# Group_01.net
KiCad netlist of a schematic drawn in EAGLE
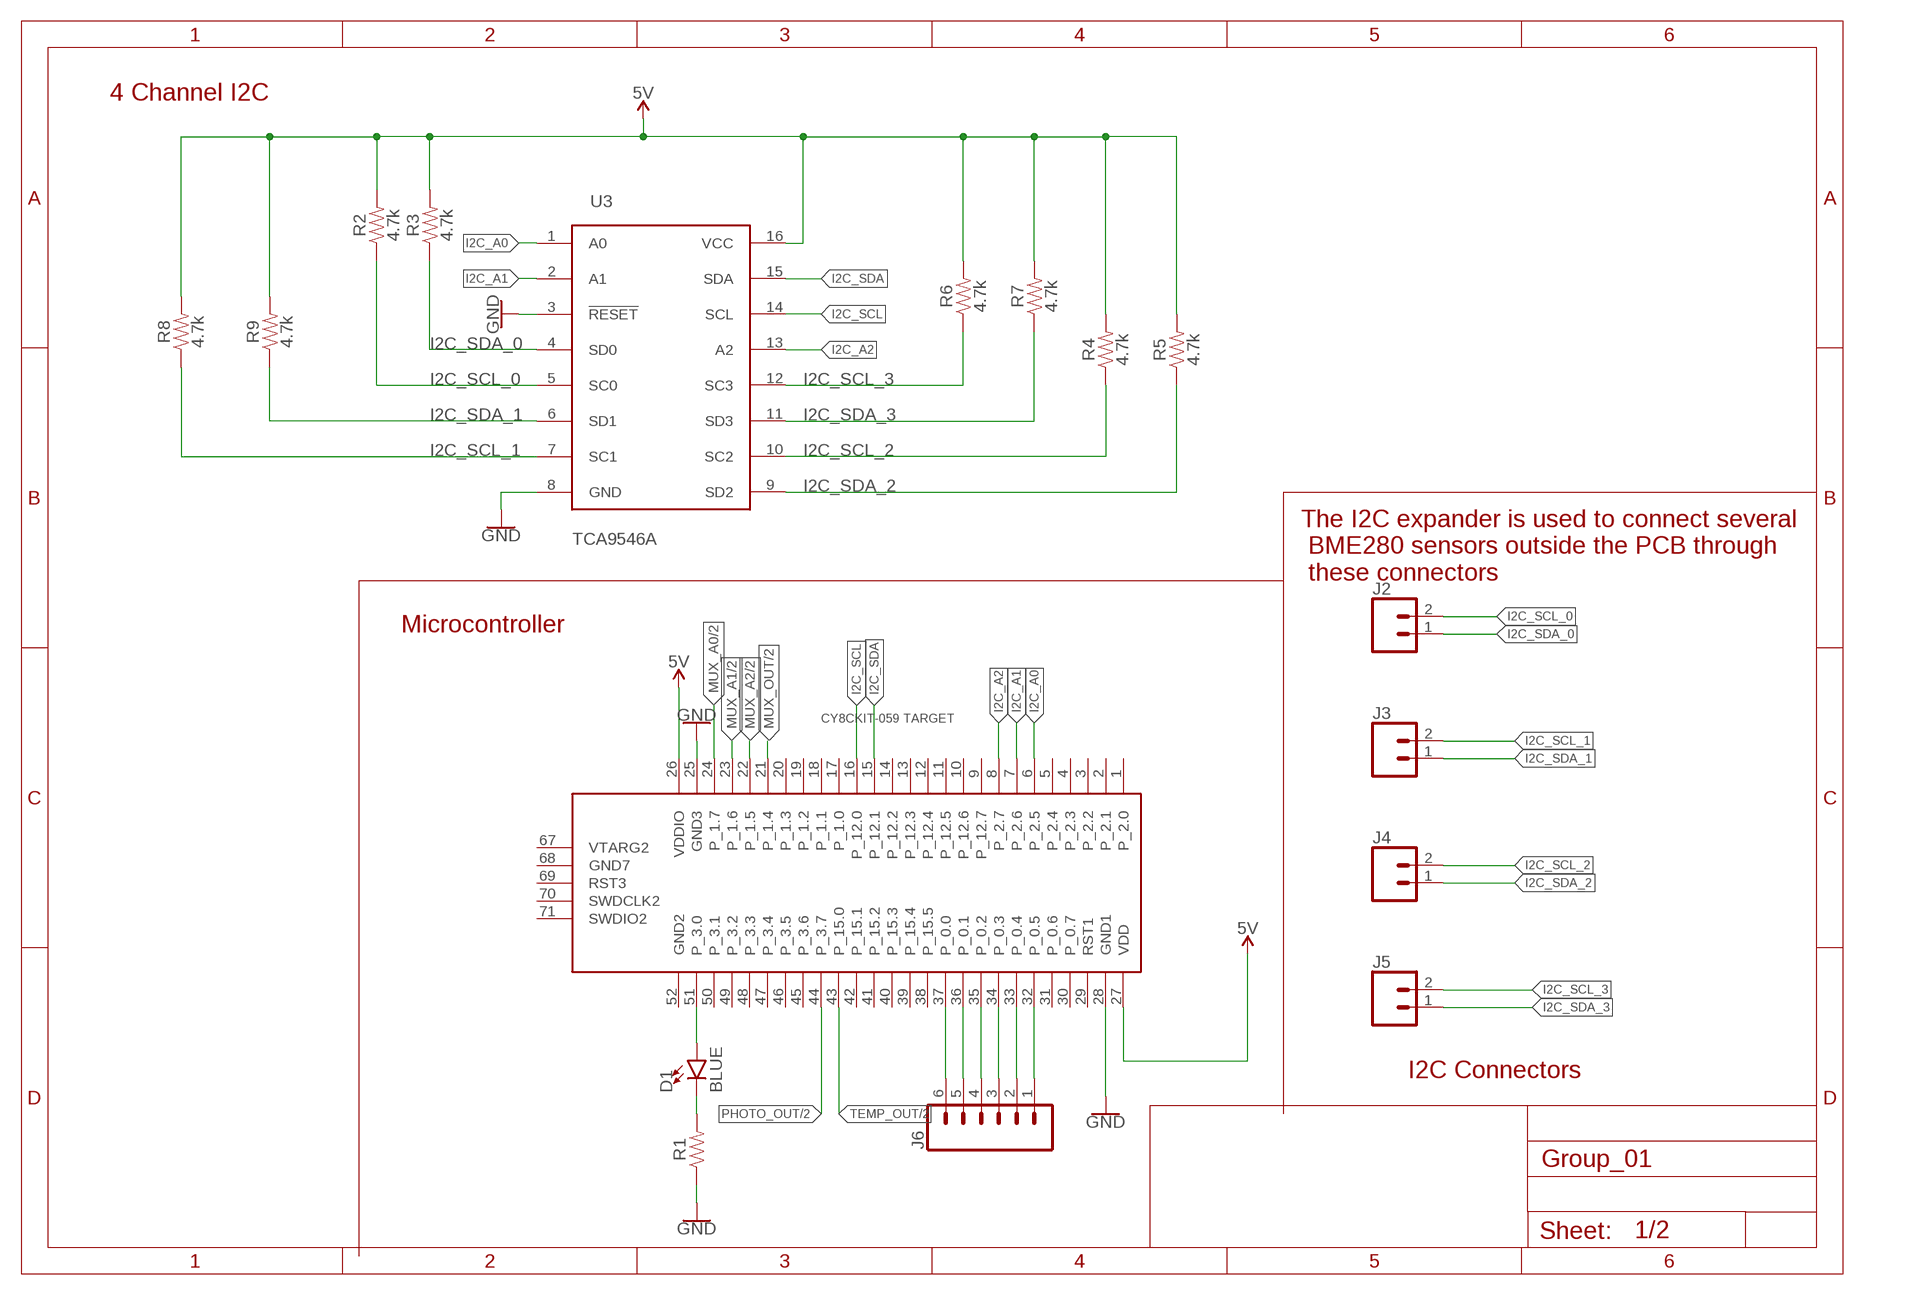
[diagram p0: schematic, sheet 1]
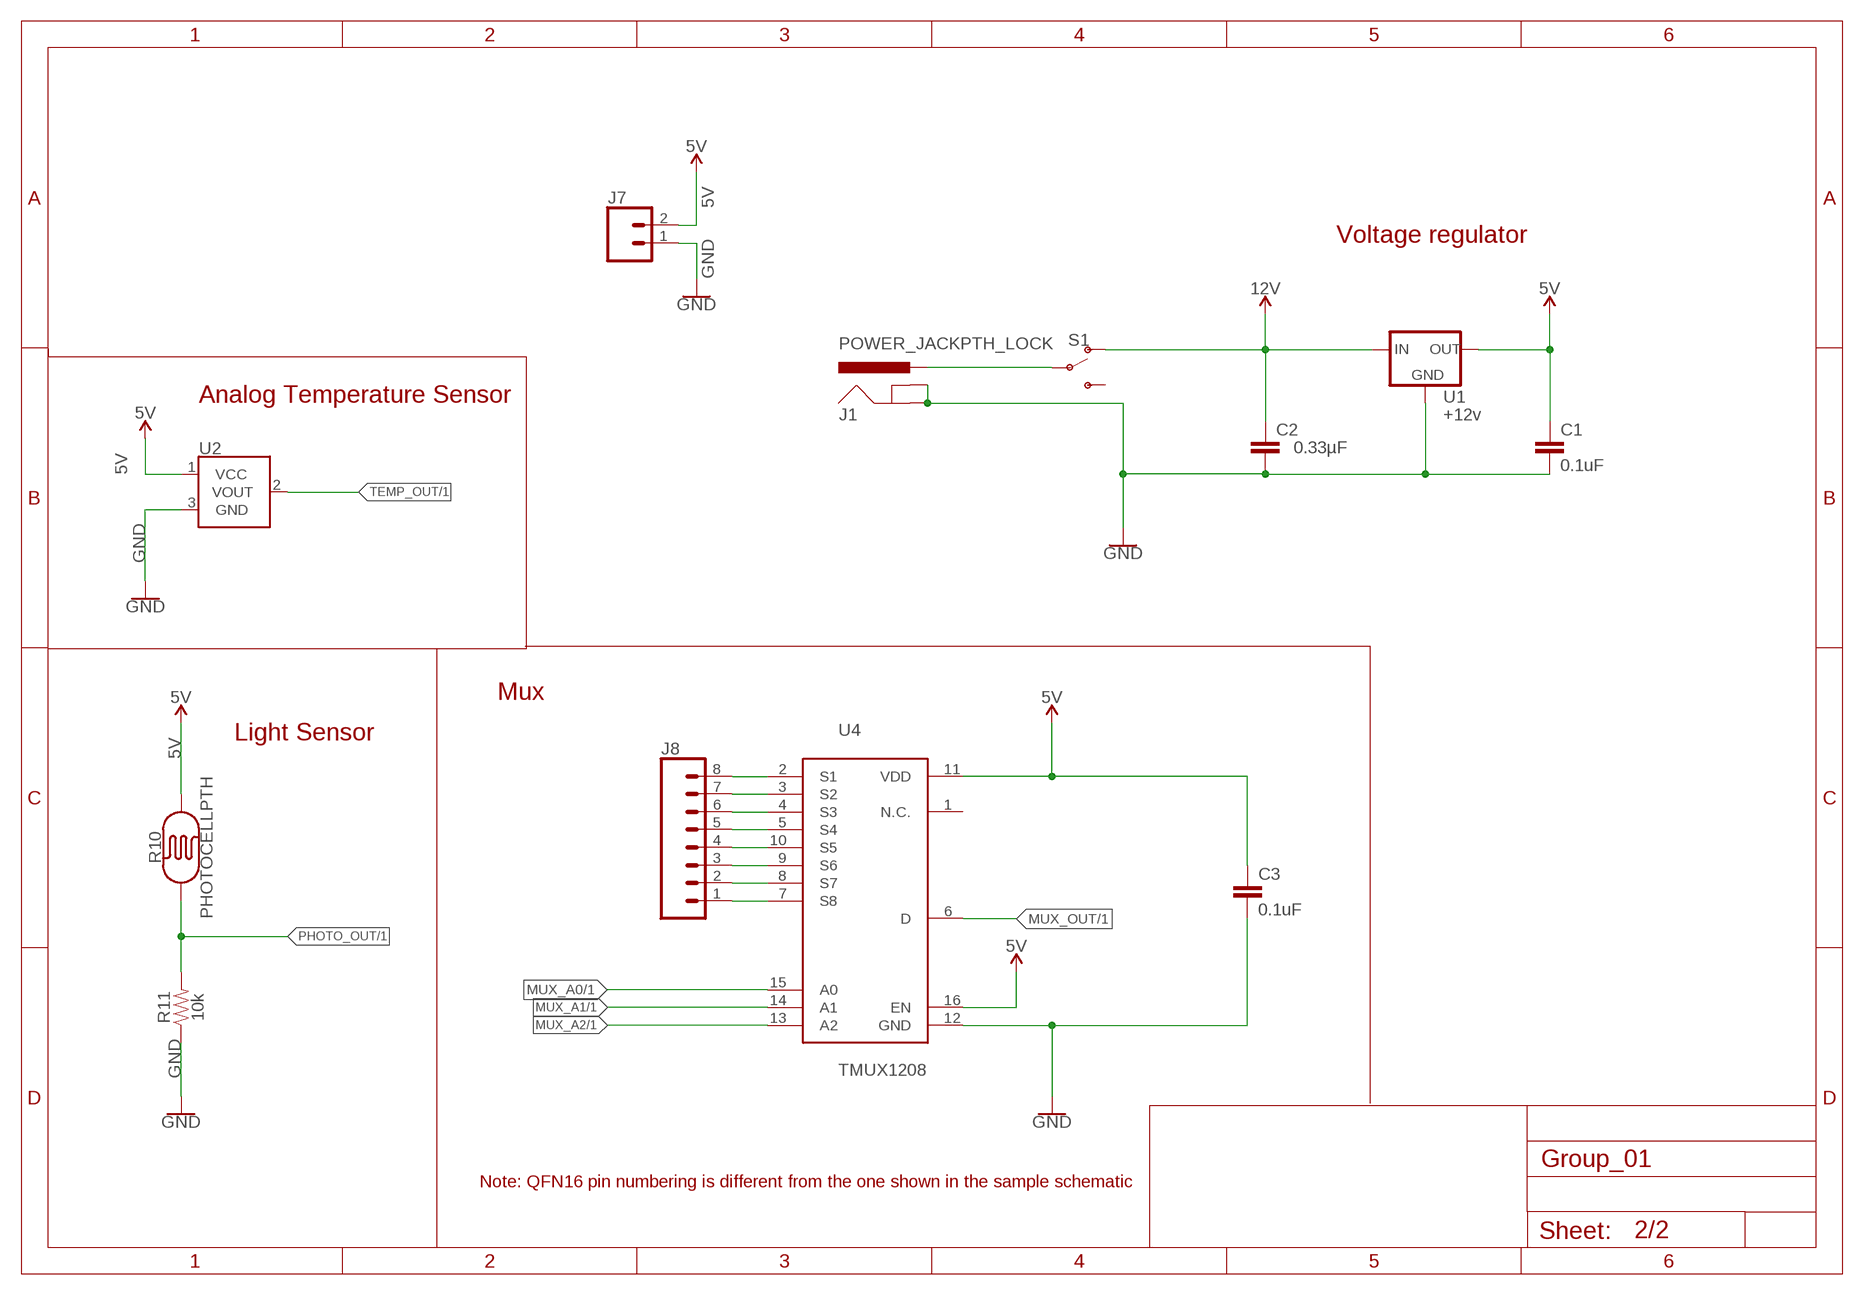
[diagram p1: schematic, sheet 2]

(export (version "E")
  (design (tool "Eeschema 10.0.6"))
  (components
    (comp (ref "D1")
      (value "BLUE")
      (footprint "eagle-import:LED-1206")
      (libsource (lib "eagle-import") (part "LED-BLUE1206"))
    )
    (comp (ref "J2")
      (value "CONN_02")
      (footprint "eagle-import:1X02")
      (libsource (lib "eagle-import") (part "CONN_02"))
    )
    (comp (ref "J3")
      (value "CONN_02")
      (footprint "eagle-import:1X02")
      (libsource (lib "eagle-import") (part "CONN_02"))
    )
    (comp (ref "J4")
      (value "CONN_02")
      (footprint "eagle-import:1X02")
      (libsource (lib "eagle-import") (part "CONN_02"))
    )
    (comp (ref "J5")
      (value "CONN_02")
      (footprint "eagle-import:1X02")
      (libsource (lib "eagle-import") (part "CONN_02"))
    )
    (comp (ref "J6")
      (value "CONN_06LOCK")
      (footprint "eagle-import:1X06_LOCK")
      (libsource (lib "eagle-import") (part "CONN_06LOCK"))
    )
    (comp (ref "R1")
      (value "RESISTORAXIAL-0.3")
      (footprint "eagle-import:AXIAL-0.3")
      (libsource (lib "eagle-import") (part "RESISTORAXIAL-0.3"))
    )
    (comp (ref "R2")
      (value "4.7k")
      (footprint "eagle-import:0603")
      (libsource (lib "eagle-import") (part "4.7KOHM-0603-1/10W-1%"))
    )
    (comp (ref "R3")
      (value "4.7k")
      (footprint "eagle-import:0603")
      (libsource (lib "eagle-import") (part "4.7KOHM-0603-1/10W-1%"))
    )
    (comp (ref "R4")
      (value "4.7k")
      (footprint "eagle-import:0603")
      (libsource (lib "eagle-import") (part "4.7KOHM-0603-1/10W-1%"))
    )
    (comp (ref "R5")
      (value "4.7k")
      (footprint "eagle-import:0603")
      (libsource (lib "eagle-import") (part "4.7KOHM-0603-1/10W-1%"))
    )
    (comp (ref "R6")
      (value "4.7k")
      (footprint "eagle-import:0603")
      (libsource (lib "eagle-import") (part "4.7KOHM-0603-1/10W-1%"))
    )
    (comp (ref "R7")
      (value "4.7k")
      (footprint "eagle-import:0603")
      (libsource (lib "eagle-import") (part "4.7KOHM-0603-1/10W-1%"))
    )
    (comp (ref "R8")
      (value "4.7k")
      (footprint "eagle-import:0603")
      (libsource (lib "eagle-import") (part "4.7KOHM-0603-1/10W-1%"))
    )
    (comp (ref "R9")
      (value "4.7k")
      (footprint "eagle-import:0603")
      (libsource (lib "eagle-import") (part "4.7KOHM-0603-1/10W-1%"))
    )
    (comp (ref "U$2")
      (value "CY8CKIT-059_TARGET")
      (footprint "eagle-import:CY8CKIT-059_TARGET")
      (libsource (lib "eagle-import") (part "CY8CKIT-059_TARGET"))
    )
    (comp (ref "U3")
      (value "TCA9546A")
      (footprint "eagle-import:TSSOP16")
      (libsource (lib "eagle-import") (part "TCA9546A"))
    )
    (comp (ref "C1")
      (value "0.1uF")
      (footprint "eagle-import:CAP-PTH-SMALL-KIT")
      (libsource (lib "eagle-import") (part "0.1UF-KIT-EZ-50V-20%"))
    )
    (comp (ref "C2")
      (value "0.33µF")
      (footprint "eagle-import:0805")
      (libsource (lib "eagle-import") (part "0.33UF/330NF-0805-50V-10%"))
    )
    (comp (ref "C3")
      (value "0.1uF")
      (footprint "eagle-import:CAP-PTH-SMALL-KIT")
      (libsource (lib "eagle-import") (part "0.1UF-KIT-EZ-50V-20%"))
    )
    (comp (ref "J1")
      (value "POWER_JACKPTH_LOCK")
      (footprint "eagle-import:POWER_JACK_PTH_LOCK")
      (libsource (lib "eagle-import") (part "POWER_JACKPTH_LOCK"))
    )
    (comp (ref "J7")
      (value "CONN_02")
      (footprint "eagle-import:1X02")
      (libsource (lib "eagle-import") (part "CONN_02"))
    )
    (comp (ref "J8")
      (value "CONN_08LOCK")
      (footprint "eagle-import:1X08_LOCK")
      (libsource (lib "eagle-import") (part "CONN_08LOCK"))
    )
    (comp (ref "R10")
      (value "PHOTOCELLPTH")
      (footprint "eagle-import:PHOTOCELL")
      (libsource (lib "eagle-import") (part "PHOTOCELLPTH"))
    )
    (comp (ref "R11")
      (value "10k")
      (footprint "eagle-import:0603")
      (libsource (lib "eagle-import") (part "10KOHM-0603-1/10W-1%"))
    )
    (comp (ref "S1")
      (value "SWITCH-SPDT-PTH-11.6X4.0MM")
      (footprint "eagle-import:SWITCH_SPDT_PTH_11.6X4.0MM")
      (libsource (lib "eagle-import") (part "SWITCH-SPDT-PTH-11.6X4.0MM"))
    )
    (comp (ref "U1")
      (value "+12v")
      (footprint "eagle-import:TO-252")
      (libsource (lib "eagle-import") (part "V_REG_78XX7812"))
    )
    (comp (ref "U2")
      (value "TMP36GT9")
      (footprint "eagle-import:TO-92")
      (libsource (lib "eagle-import") (part "TMP36GT9"))
    )
    (comp (ref "U4")
      (value "TMUX1208")
      (footprint "eagle-import:QFN16")
      (libsource (lib "eagle-import") (part "TMUX1208"))
    )
  )
  (nets
    (net (code "1") (name "5V") (class "Default")
      (node (ref "C1") (pin "1") (pinfunction "1_1") (pintype "passive"))
      (node (ref "C3") (pin "1") (pinfunction "1_1") (pintype "passive"))
      (node (ref "J7") (pin "2") (pinfunction "2_2") (pintype "passive"))
      (node (ref "R10") (pin "2") (pinfunction "P$2_2") (pintype "bidirectional"))
      (node (ref "R2") (pin "2") (pinfunction "2_2") (pintype "passive"))
      (node (ref "R3") (pin "2") (pinfunction "2_2") (pintype "passive"))
      (node (ref "R4") (pin "2") (pinfunction "2_2") (pintype "passive"))
      (node (ref "R5") (pin "2") (pinfunction "2_2") (pintype "passive"))
      (node (ref "R6") (pin "2") (pinfunction "2_2") (pintype "passive"))
      (node (ref "R7") (pin "2") (pinfunction "2_2") (pintype "passive"))
      (node (ref "R8") (pin "2") (pinfunction "2_2") (pintype "passive"))
      (node (ref "R9") (pin "2") (pinfunction "2_2") (pintype "passive"))
      (node (ref "U$2") (pin "26") (pinfunction "VDDIO_26") (pintype "bidirectional"))
      (node (ref "U$2") (pin "27") (pinfunction "VDD_27") (pintype "bidirectional"))
      (node (ref "U1") (pin "2") (pinfunction "OUT_2") (pintype "passive"))
      (node (ref "U2") (pin "1") (pinfunction "VCC_1") (pintype "bidirectional"))
      (node (ref "U3") (pin "16") (pinfunction "VCC_16") (pintype "bidirectional"))
      (node (ref "U4") (pin "11") (pinfunction "VDD_11") (pintype "bidirectional"))
      (node (ref "U4") (pin "16") (pinfunction "EN_16") (pintype "bidirectional"))
    )
    (net (code "2") (name "12V") (class "Default")
      (node (ref "C2") (pin "1") (pinfunction "1_1") (pintype "passive"))
      (node (ref "S1") (pin "1") (pinfunction "O_1") (pintype "passive"))
      (node (ref "U1") (pin "1") (pinfunction "IN_1") (pintype "input"))
    )
    (net (code "3") (name "GND") (class "Default")
      (node (ref "C1") (pin "2") (pinfunction "2_2") (pintype "passive"))
      (node (ref "C2") (pin "2") (pinfunction "2_2") (pintype "passive"))
      (node (ref "C3") (pin "2") (pinfunction "2_2") (pintype "passive"))
      (node (ref "J1") (pin "GND") (pinfunction "GND_GND") (pintype "bidirectional"))
      (node (ref "J1") (pin "GNDBREAK") (pinfunction "GNDBREAK_GNDBREAK") (pintype "bidirectional"))
      (node (ref "J7") (pin "1") (pinfunction "1_1") (pintype "passive"))
      (node (ref "R1") (pin "P$1") (pinfunction "1_P$1") (pintype "passive"))
      (node (ref "R11") (pin "1") (pinfunction "1_1") (pintype "passive"))
      (node (ref "U$2") (pin "25") (pinfunction "GND3_25") (pintype "bidirectional"))
      (node (ref "U$2") (pin "28") (pinfunction "GND1_28") (pintype "bidirectional"))
      (node (ref "U1") (pin "3") (pinfunction "GND_3") (pintype "input"))
      (node (ref "U2") (pin "3") (pinfunction "GND_3") (pintype "bidirectional"))
      (node (ref "U3") (pin "3") (pinfunction "~{RESET}_3") (pintype "bidirectional"))
      (node (ref "U3") (pin "8") (pinfunction "GND_8") (pintype "bidirectional"))
      (node (ref "U4") (pin "12") (pinfunction "GND_12") (pintype "bidirectional"))
    )
    (net (code "4") (name "I2C_A0") (class "Default")
      (node (ref "U$2") (pin "6") (pinfunction "P_2.5_6") (pintype "bidirectional"))
      (node (ref "U3") (pin "1") (pinfunction "A0_1") (pintype "bidirectional"))
    )
    (net (code "5") (name "I2C_A1") (class "Default")
      (node (ref "U$2") (pin "7") (pinfunction "P_2.6_7") (pintype "bidirectional"))
      (node (ref "U3") (pin "2") (pinfunction "A1_2") (pintype "bidirectional"))
    )
    (net (code "6") (name "I2C_A2") (class "Default")
      (node (ref "U$2") (pin "8") (pinfunction "P_2.7_8") (pintype "bidirectional"))
      (node (ref "U3") (pin "13") (pinfunction "A2_13") (pintype "bidirectional"))
    )
    (net (code "7") (name "I2C_SCL") (class "Default")
      (node (ref "U$2") (pin "16") (pinfunction "P_12.0_16") (pintype "bidirectional"))
      (node (ref "U3") (pin "14") (pinfunction "SCL_14") (pintype "bidirectional"))
    )
    (net (code "8") (name "I2C_SCL_0") (class "Default")
      (node (ref "J2") (pin "2") (pinfunction "2_2") (pintype "passive"))
      (node (ref "R2") (pin "1") (pinfunction "1_1") (pintype "passive"))
      (node (ref "U3") (pin "5") (pinfunction "SC0_5") (pintype "bidirectional"))
    )
    (net (code "9") (name "I2C_SCL_1") (class "Default")
      (node (ref "J3") (pin "2") (pinfunction "2_2") (pintype "passive"))
      (node (ref "R8") (pin "1") (pinfunction "1_1") (pintype "passive"))
      (node (ref "U3") (pin "7") (pinfunction "SC1_7") (pintype "bidirectional"))
    )
    (net (code "10") (name "I2C_SCL_2") (class "Default")
      (node (ref "J4") (pin "2") (pinfunction "2_2") (pintype "passive"))
      (node (ref "R4") (pin "1") (pinfunction "1_1") (pintype "passive"))
      (node (ref "U3") (pin "10") (pinfunction "SC2_10") (pintype "bidirectional"))
    )
    (net (code "11") (name "I2C_SCL_3") (class "Default")
      (node (ref "J5") (pin "2") (pinfunction "2_2") (pintype "passive"))
      (node (ref "R6") (pin "1") (pinfunction "1_1") (pintype "passive"))
      (node (ref "U3") (pin "12") (pinfunction "SC3_12") (pintype "bidirectional"))
    )
    (net (code "12") (name "I2C_SDA") (class "Default")
      (node (ref "U$2") (pin "15") (pinfunction "P_12.1_15") (pintype "bidirectional"))
      (node (ref "U3") (pin "15") (pinfunction "SDA_15") (pintype "bidirectional"))
    )
    (net (code "13") (name "I2C_SDA_0") (class "Default")
      (node (ref "J2") (pin "1") (pinfunction "1_1") (pintype "passive"))
      (node (ref "R3") (pin "1") (pinfunction "1_1") (pintype "passive"))
      (node (ref "U3") (pin "4") (pinfunction "SD0_4") (pintype "bidirectional"))
    )
    (net (code "14") (name "I2C_SDA_1") (class "Default")
      (node (ref "J3") (pin "1") (pinfunction "1_1") (pintype "passive"))
      (node (ref "R9") (pin "1") (pinfunction "1_1") (pintype "passive"))
      (node (ref "U3") (pin "6") (pinfunction "SD1_6") (pintype "bidirectional"))
    )
    (net (code "15") (name "I2C_SDA_2") (class "Default")
      (node (ref "J4") (pin "1") (pinfunction "1_1") (pintype "passive"))
      (node (ref "R5") (pin "1") (pinfunction "1_1") (pintype "passive"))
      (node (ref "U3") (pin "9") (pinfunction "SD2_9") (pintype "bidirectional"))
    )
    (net (code "16") (name "I2C_SDA_3") (class "Default")
      (node (ref "J5") (pin "1") (pinfunction "1_1") (pintype "passive"))
      (node (ref "R7") (pin "1") (pinfunction "1_1") (pintype "passive"))
      (node (ref "U3") (pin "11") (pinfunction "SD3_11") (pintype "bidirectional"))
    )
    (net (code "17") (name "MUX_A0") (class "Default")
      (node (ref "U$2") (pin "24") (pinfunction "P_1.7_24") (pintype "bidirectional"))
      (node (ref "U4") (pin "15") (pinfunction "A0_15") (pintype "bidirectional"))
    )
    (net (code "18") (name "MUX_A1") (class "Default")
      (node (ref "U$2") (pin "23") (pinfunction "P_1.6_23") (pintype "bidirectional"))
      (node (ref "U4") (pin "14") (pinfunction "A1_14") (pintype "bidirectional"))
    )
    (net (code "19") (name "MUX_A2") (class "Default")
      (node (ref "U$2") (pin "22") (pinfunction "P_1.5_22") (pintype "bidirectional"))
      (node (ref "U4") (pin "13") (pinfunction "A2_13") (pintype "bidirectional"))
    )
    (net (code "20") (name "MUX_OUT") (class "Default")
      (node (ref "U$2") (pin "21") (pinfunction "P_1.4_21") (pintype "bidirectional"))
      (node (ref "U4") (pin "6") (pinfunction "D_6") (pintype "bidirectional"))
    )
    (net (code "21") (name "Net-(R1-2)") (class "Default")
      (node (ref "D1") (pin "C") (pinfunction "C_C") (pintype "passive"))
      (node (ref "R1") (pin "P$2") (pinfunction "2_P$2") (pintype "passive"))
    )
    (net (code "22") (name "Net-(S1-P)") (class "Default")
      (node (ref "J1") (pin "PWR") (pinfunction "PWR_PWR") (pintype "bidirectional"))
      (node (ref "S1") (pin "2") (pinfunction "P_2") (pintype "passive"))
    )
    (net (code "23") (name "Net-(U$2-P_0.0)") (class "Default")
      (node (ref "J6") (pin "6") (pinfunction "6_6") (pintype "passive"))
      (node (ref "U$2") (pin "37") (pinfunction "P_0.0_37") (pintype "bidirectional"))
    )
    (net (code "24") (name "Net-(U$2-P_0.1)") (class "Default")
      (node (ref "J6") (pin "5") (pinfunction "5_5") (pintype "passive"))
      (node (ref "U$2") (pin "36") (pinfunction "P_0.1_36") (pintype "bidirectional"))
    )
    (net (code "25") (name "Net-(U$2-P_0.2)") (class "Default")
      (node (ref "J6") (pin "4") (pinfunction "4_4") (pintype "passive"))
      (node (ref "U$2") (pin "35") (pinfunction "P_0.2_35") (pintype "bidirectional"))
    )
    (net (code "26") (name "Net-(U$2-P_0.3)") (class "Default")
      (node (ref "J6") (pin "3") (pinfunction "3_3") (pintype "passive"))
      (node (ref "U$2") (pin "34") (pinfunction "P_0.3_34") (pintype "bidirectional"))
    )
    (net (code "27") (name "Net-(U$2-P_0.4)") (class "Default")
      (node (ref "J6") (pin "2") (pinfunction "2_2") (pintype "passive"))
      (node (ref "U$2") (pin "33") (pinfunction "P_0.4_33") (pintype "bidirectional"))
    )
    (net (code "28") (name "Net-(U$2-P_0.5)") (class "Default")
      (node (ref "J6") (pin "1") (pinfunction "1_1") (pintype "passive"))
      (node (ref "U$2") (pin "32") (pinfunction "P_0.5_32") (pintype "bidirectional"))
    )
    (net (code "29") (name "Net-(U$2-P_3.0)") (class "Default")
      (node (ref "D1") (pin "A") (pinfunction "A_A") (pintype "passive"))
      (node (ref "U$2") (pin "51") (pinfunction "P_3.0_51") (pintype "bidirectional"))
    )
    (net (code "30") (name "Net-(U4-S1)") (class "Default")
      (node (ref "J8") (pin "8") (pinfunction "8_8") (pintype "passive"))
      (node (ref "U4") (pin "2") (pinfunction "S1_2") (pintype "bidirectional"))
    )
    (net (code "31") (name "Net-(U4-S2)") (class "Default")
      (node (ref "J8") (pin "7") (pinfunction "7_7") (pintype "passive"))
      (node (ref "U4") (pin "3") (pinfunction "S2_3") (pintype "bidirectional"))
    )
    (net (code "32") (name "Net-(U4-S3)") (class "Default")
      (node (ref "J8") (pin "6") (pinfunction "6_6") (pintype "passive"))
      (node (ref "U4") (pin "4") (pinfunction "S3_4") (pintype "bidirectional"))
    )
    (net (code "33") (name "Net-(U4-S4)") (class "Default")
      (node (ref "J8") (pin "5") (pinfunction "5_5") (pintype "passive"))
      (node (ref "U4") (pin "5") (pinfunction "S4_5") (pintype "bidirectional"))
    )
    (net (code "34") (name "Net-(U4-S5)") (class "Default")
      (node (ref "J8") (pin "4") (pinfunction "4_4") (pintype "passive"))
      (node (ref "U4") (pin "10") (pinfunction "S5_10") (pintype "bidirectional"))
    )
    (net (code "35") (name "Net-(U4-S6)") (class "Default")
      (node (ref "J8") (pin "3") (pinfunction "3_3") (pintype "passive"))
      (node (ref "U4") (pin "9") (pinfunction "S6_9") (pintype "bidirectional"))
    )
    (net (code "36") (name "Net-(U4-S7)") (class "Default")
      (node (ref "J8") (pin "2") (pinfunction "2_2") (pintype "passive"))
      (node (ref "U4") (pin "8") (pinfunction "S7_8") (pintype "bidirectional"))
    )
    (net (code "37") (name "Net-(U4-S8)") (class "Default")
      (node (ref "J8") (pin "1") (pinfunction "1_1") (pintype "passive"))
      (node (ref "U4") (pin "7") (pinfunction "S8_7") (pintype "bidirectional"))
    )
    (net (code "38") (name "PHOTO_OUT") (class "Default")
      (node (ref "R10") (pin "1") (pinfunction "P$1_1") (pintype "bidirectional"))
      (node (ref "R11") (pin "2") (pinfunction "2_2") (pintype "passive"))
      (node (ref "U$2") (pin "44") (pinfunction "P_3.7_44") (pintype "bidirectional"))
    )
    (net (code "39") (name "TEMP_OUT") (class "Default")
      (node (ref "U$2") (pin "43") (pinfunction "P_15.0_43") (pintype "bidirectional"))
      (node (ref "U2") (pin "2") (pinfunction "VOUT_2") (pintype "bidirectional"))
    )
    (net (code "40") (name "unconnected-(S1-S-Pad3)") (class "Default")
      (node (ref "S1") (pin "3") (pinfunction "S_3") (pintype "passive"))
    )
    (net (code "41") (name "unconnected-(U$2-GND2-Pad52)") (class "Default")
      (node (ref "U$2") (pin "52") (pinfunction "GND2_52") (pintype "bidirectional"))
    )
    (net (code "42") (name "unconnected-(U$2-GND7-Pad68)") (class "Default")
      (node (ref "U$2") (pin "68") (pinfunction "GND7_68") (pintype "bidirectional"))
    )
    (net (code "43") (name "unconnected-(U$2-P_0.6-Pad31)") (class "Default")
      (node (ref "U$2") (pin "31") (pinfunction "P_0.6_31") (pintype "bidirectional"))
    )
    (net (code "44") (name "unconnected-(U$2-P_0.7-Pad30)") (class "Default")
      (node (ref "U$2") (pin "30") (pinfunction "P_0.7_30") (pintype "bidirectional"))
    )
    (net (code "45") (name "unconnected-(U$2-P_1.0-Pad17)") (class "Default")
      (node (ref "U$2") (pin "17") (pinfunction "P_1.0_17") (pintype "bidirectional"))
    )
    (net (code "46") (name "unconnected-(U$2-P_1.1-Pad18)") (class "Default")
      (node (ref "U$2") (pin "18") (pinfunction "P_1.1_18") (pintype "bidirectional"))
    )
    (net (code "47") (name "unconnected-(U$2-P_1.2-Pad19)") (class "Default")
      (node (ref "U$2") (pin "19") (pinfunction "P_1.2_19") (pintype "bidirectional"))
    )
    (net (code "48") (name "unconnected-(U$2-P_1.3-Pad20)") (class "Default")
      (node (ref "U$2") (pin "20") (pinfunction "P_1.3_20") (pintype "bidirectional"))
    )
    (net (code "49") (name "unconnected-(U$2-P_2.0-Pad1)") (class "Default")
      (node (ref "U$2") (pin "1") (pinfunction "P_2.0_1") (pintype "bidirectional"))
    )
    (net (code "50") (name "unconnected-(U$2-P_2.1-Pad2)") (class "Default")
      (node (ref "U$2") (pin "2") (pinfunction "P_2.1_2") (pintype "bidirectional"))
    )
    (net (code "51") (name "unconnected-(U$2-P_2.2-Pad3)") (class "Default")
      (node (ref "U$2") (pin "3") (pinfunction "P_2.2_3") (pintype "bidirectional"))
    )
    (net (code "52") (name "unconnected-(U$2-P_2.3-Pad4)") (class "Default")
      (node (ref "U$2") (pin "4") (pinfunction "P_2.3_4") (pintype "bidirectional"))
    )
    (net (code "53") (name "unconnected-(U$2-P_2.4-Pad5)") (class "Default")
      (node (ref "U$2") (pin "5") (pinfunction "P_2.4_5") (pintype "bidirectional"))
    )
    (net (code "54") (name "unconnected-(U$2-P_3.1-Pad50)") (class "Default")
      (node (ref "U$2") (pin "50") (pinfunction "P_3.1_50") (pintype "bidirectional"))
    )
    (net (code "55") (name "unconnected-(U$2-P_3.2-Pad49)") (class "Default")
      (node (ref "U$2") (pin "49") (pinfunction "P_3.2_49") (pintype "bidirectional"))
    )
    (net (code "56") (name "unconnected-(U$2-P_3.3-Pad48)") (class "Default")
      (node (ref "U$2") (pin "48") (pinfunction "P_3.3_48") (pintype "bidirectional"))
    )
    (net (code "57") (name "unconnected-(U$2-P_3.4-Pad47)") (class "Default")
      (node (ref "U$2") (pin "47") (pinfunction "P_3.4_47") (pintype "bidirectional"))
    )
    (net (code "58") (name "unconnected-(U$2-P_3.5-Pad46)") (class "Default")
      (node (ref "U$2") (pin "46") (pinfunction "P_3.5_46") (pintype "bidirectional"))
    )
    (net (code "59") (name "unconnected-(U$2-P_3.6-Pad45)") (class "Default")
      (node (ref "U$2") (pin "45") (pinfunction "P_3.6_45") (pintype "bidirectional"))
    )
    (net (code "60") (name "unconnected-(U$2-P_12.2-Pad14)") (class "Default")
      (node (ref "U$2") (pin "14") (pinfunction "P_12.2_14") (pintype "bidirectional"))
    )
    (net (code "61") (name "unconnected-(U$2-P_12.3-Pad13)") (class "Default")
      (node (ref "U$2") (pin "13") (pinfunction "P_12.3_13") (pintype "bidirectional"))
    )
    (net (code "62") (name "unconnected-(U$2-P_12.4-Pad12)") (class "Default")
      (node (ref "U$2") (pin "12") (pinfunction "P_12.4_12") (pintype "bidirectional"))
    )
    (net (code "63") (name "unconnected-(U$2-P_12.5-Pad11)") (class "Default")
      (node (ref "U$2") (pin "11") (pinfunction "P_12.5_11") (pintype "bidirectional"))
    )
    (net (code "64") (name "unconnected-(U$2-P_12.6-Pad10)") (class "Default")
      (node (ref "U$2") (pin "10") (pinfunction "P_12.6_10") (pintype "bidirectional"))
    )
    (net (code "65") (name "unconnected-(U$2-P_12.7-Pad9)") (class "Default")
      (node (ref "U$2") (pin "9") (pinfunction "P_12.7_9") (pintype "bidirectional"))
    )
    (net (code "66") (name "unconnected-(U$2-P_15.1-Pad42)") (class "Default")
      (node (ref "U$2") (pin "42") (pinfunction "P_15.1_42") (pintype "bidirectional"))
    )
    (net (code "67") (name "unconnected-(U$2-P_15.2-Pad41)") (class "Default")
      (node (ref "U$2") (pin "41") (pinfunction "P_15.2_41") (pintype "bidirectional"))
    )
    (net (code "68") (name "unconnected-(U$2-P_15.3-Pad40)") (class "Default")
      (node (ref "U$2") (pin "40") (pinfunction "P_15.3_40") (pintype "bidirectional"))
    )
    (net (code "69") (name "unconnected-(U$2-P_15.4-Pad39)") (class "Default")
      (node (ref "U$2") (pin "39") (pinfunction "P_15.4_39") (pintype "bidirectional"))
    )
    (net (code "70") (name "unconnected-(U$2-P_15.5-Pad38)") (class "Default")
      (node (ref "U$2") (pin "38") (pinfunction "P_15.5_38") (pintype "bidirectional"))
    )
    (net (code "71") (name "unconnected-(U$2-RST1-Pad29)") (class "Default")
      (node (ref "U$2") (pin "29") (pinfunction "RST1_29") (pintype "bidirectional"))
    )
    (net (code "72") (name "unconnected-(U$2-RST3-Pad69)") (class "Default")
      (node (ref "U$2") (pin "69") (pinfunction "RST3_69") (pintype "bidirectional"))
    )
    (net (code "73") (name "unconnected-(U$2-SWDCLK2-Pad70)") (class "Default")
      (node (ref "U$2") (pin "70") (pinfunction "SWDCLK2_70") (pintype "bidirectional"))
    )
    (net (code "74") (name "unconnected-(U$2-SWDIO2-Pad71)") (class "Default")
      (node (ref "U$2") (pin "71") (pinfunction "SWDIO2_71") (pintype "bidirectional"))
    )
    (net (code "75") (name "unconnected-(U$2-VTARG2-Pad67)") (class "Default")
      (node (ref "U$2") (pin "67") (pinfunction "VTARG2_67") (pintype "bidirectional"))
    )
    (net (code "76") (name "unconnected-(U4-N.C.-Pad1)") (class "Default")
      (node (ref "U4") (pin "1") (pinfunction "N.C._1") (pintype "bidirectional"))
    )
  )
)
